# USB-RS485-unit.net
KiCad netlist of a schematic drawn in Altium Designer
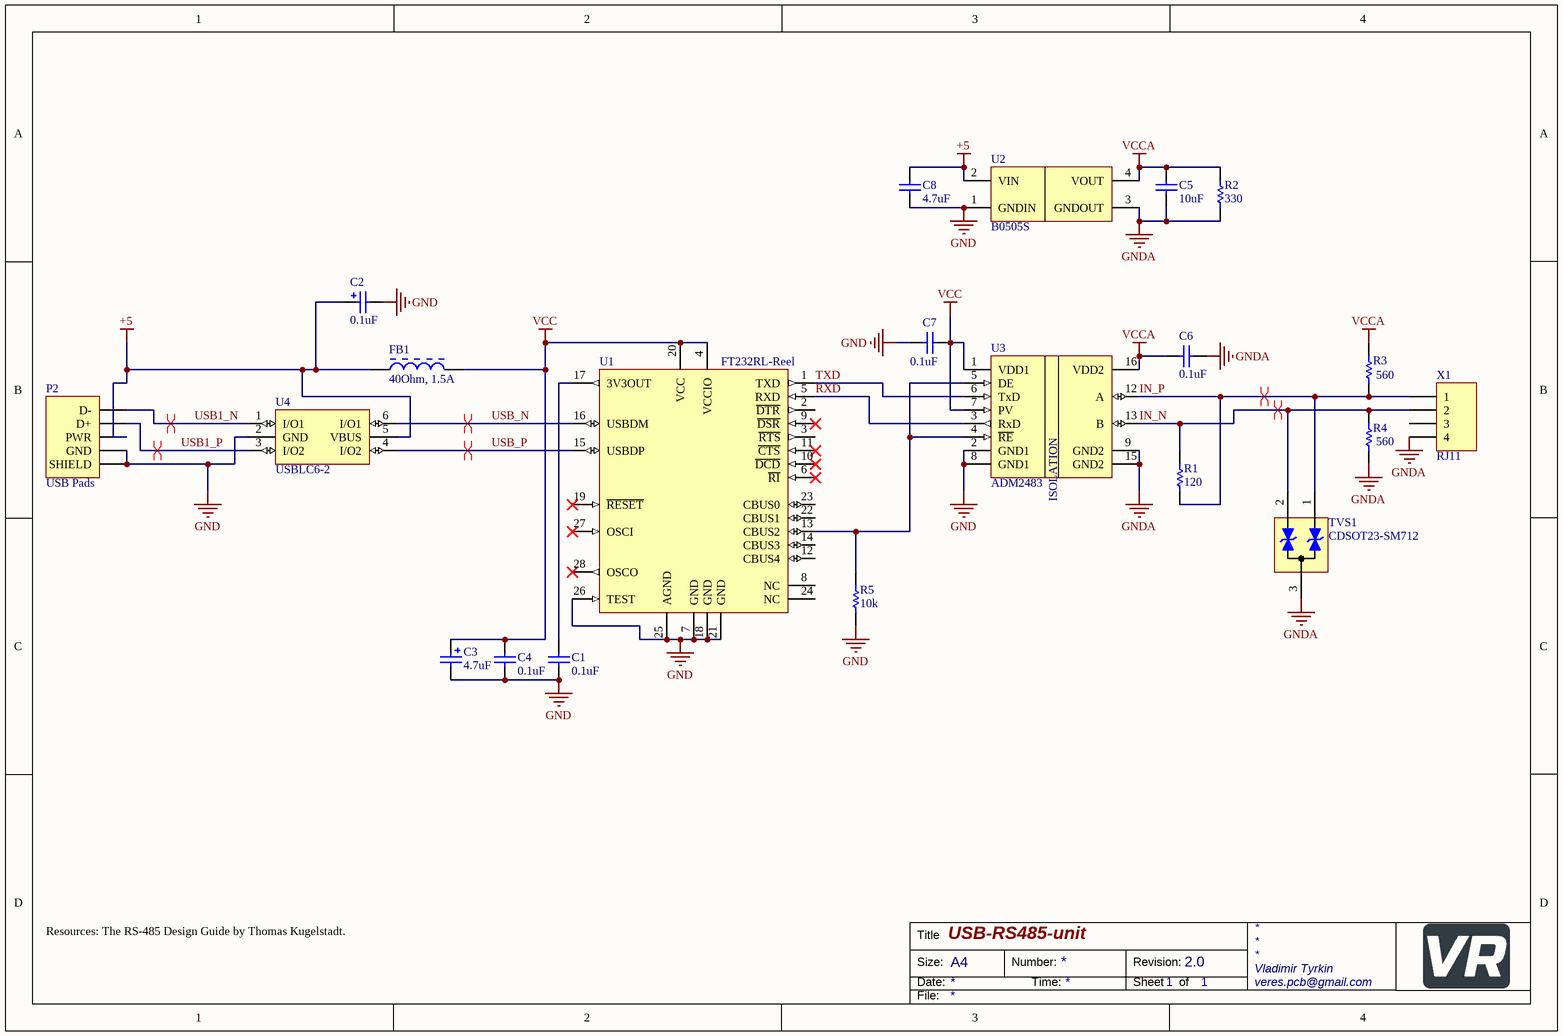
[diagram p0: USB-RS485-unit.SchDoc]

(export (version "E")
  (design (tool "Eeschema 10.0.6"))
  (components
    (comp (ref "C1")
      (value "0.1uF")
      (footprint "C1206")
      (description "Capacitor ceramic SMT")
      (fields
        (field (name "MANUFACTURER_PART_NUMBER") "GRM319R72A104KA01D")
        (field (name "MANUFACTURER") "Murata")
      )
      (libsource (lib "USB-RS485-unit") (part "Cap"))
    )
    (comp (ref "C2")
      (value "0.1uF")
      (footprint "TC3216-1206")
      (description "Polarized Capacitor SMT")
      (fields
        (field (name "MANUFACTURER") "TECAP")
        (field (name "MANUFACTURER_PART_NUMBER") "TECAP0.1/35VA10")
      )
      (libsource (lib "USB-RS485-unit") (part "Cap Polarized"))
    )
    (comp (ref "C3")
      (value "4.7uF")
      (footprint "TC3216-1206")
      (description "Polarized Capacitor SMT")
      (fields
        (field (name "MANUFACTURER") "TECAP")
        (field (name "MANUFACTURER_PART_NUMBER") "TECAP4.7/10VA10")
      )
      (libsource (lib "USB-RS485-unit") (part "Cap Polarized"))
    )
    (comp (ref "C4")
      (value "0.1uF")
      (footprint "C1206")
      (description "Capacitor ceramic SMT")
      (fields
        (field (name "MANUFACTURER_PART_NUMBER") "GRM319R72A104KA01D")
        (field (name "MANUFACTURER") "Murata")
      )
      (libsource (lib "USB-RS485-unit") (part "Cap"))
    )
    (comp (ref "C5")
      (value "10uF")
      (footprint "C1206")
      (description "Capacitor ceramic SMT")
      (fields
        (field (name "MANUFACTURER_PART_NUMBER") "GRM31CR61E106KA12L")
        (field (name "MANUFACTURER") "Murata")
      )
      (libsource (lib "USB-RS485-unit") (part "Cap"))
    )
    (comp (ref "C6")
      (value "0.1uF")
      (footprint "C1206")
      (description "Capacitor ceramic SMT")
      (fields
        (field (name "MANUFACTURER_PART_NUMBER") "GRM319R72A104KA01D")
        (field (name "MANUFACTURER") "Murata")
      )
      (libsource (lib "USB-RS485-unit") (part "Cap"))
    )
    (comp (ref "C7")
      (value "0.1uF")
      (footprint "C1206")
      (description "Capacitor ceramic SMT")
      (fields
        (field (name "MANUFACTURER_PART_NUMBER") "GRM319R72A104KA01D")
        (field (name "MANUFACTURER") "Murata")
      )
      (libsource (lib "USB-RS485-unit") (part "Cap"))
    )
    (comp (ref "C8")
      (value "4.7uF")
      (footprint "C1206")
      (description "Capacitor ceramic SMT")
      (fields
        (field (name "MANUFACTURER_PART_NUMBER") "GRM31CR71E475KA88L")
        (field (name "MANUFACTURER") "Murata")
      )
      (libsource (lib "USB-RS485-unit") (part "Cap"))
    )
    (comp (ref "FB1")
      (value "40Ohm, 1.5A")
      (footprint "WE-CBF_0805_High Speed")
      (description "Ferrite Bead")
      (fields
        (field (name "MANUFACTURER PART NUMBER") "MI0805K400R-10")
        (field (name "MANUFACTURER") "Laird Technologies")
      )
      (libsource (lib "WE-FerriteBead (rev21a)") (part "7427920"))
    )
    (comp (ref "P2")
      (value "USB Pads")
      (footprint "USB soldering pads")
      (description "Pads for soldering USB cable")
      (libsource (lib "USB-RS485-unit") (part "USB pads"))
    )
    (comp (ref "R1")
      (value "120")
      (footprint "RES-0805")
      (description "Rectangular Thick Film Chip Resistor")
      (fields
        (field (name "MANUFACTURER") "Yageo")
        (field (name "MANUFACTURER_PART_NUMBER") "RC0805FR-07120RL")
      )
      (libsource (lib "USB-RS485-unit") (part "Res"))
    )
    (comp (ref "R2")
      (value "330")
      (footprint "RES-1206")
      (description "Rectangular Thick Film Chip Resistor")
      (fields
        (field (name "MANUFACTURER") "Yageo")
        (field (name "MANUFACTURER_PART_NUMBER") "RC0805FR-07330RL")
      )
      (libsource (lib "USB-RS485-unit") (part "Res"))
    )
    (comp (ref "R3")
      (value "560")
      (footprint "RES-0805")
      (description "Rectangular Thick Film Chip Resistor")
      (fields
        (field (name "MANUFACTURER") "Yageo")
        (field (name "MANUFACTURER_PART_NUMBER") "RC0805FR-07560RL")
      )
      (libsource (lib "USB-RS485-unit") (part "Res"))
    )
    (comp (ref "R4")
      (value "560")
      (footprint "RES-0805")
      (description "Rectangular Thick Film Chip Resistor")
      (fields
        (field (name "MANUFACTURER") "Yageo")
        (field (name "MANUFACTURER_PART_NUMBER") "RC0805FR-07560RL")
      )
      (libsource (lib "USB-RS485-unit") (part "Res"))
    )
    (comp (ref "R5")
      (value "10k")
      (footprint "RES-0805")
      (description "Rectangular Thick Film Chip Resistor")
      (fields
        (field (name "MANUFACTURER") "Yageo")
        (field (name "MANUFACTURER_PART_NUMBER") "RC0805FR-0710KL")
      )
      (libsource (lib "USB-RS485-unit") (part "Res"))
    )
    (comp (ref "TVS1")
      (value "CDSOT23-SM712")
      (footprint "SOT-23B_N")
      (description "Surface Mount TVS Diode")
      (fields (field (name "MANUFACTURER") "Bourns"))
      (libsource (lib "USB-RS485-unit") (part "CDSOT23-SM712"))
    )
    (comp (ref "U1")
      (value "FT232RL-Reel")
      (footprint "SSOP-28_L")
      (description "USB UART Asynchronous Serial Data Transfer Chip, SSOP-28, Tape and Reel")
      (fields (field (name "MANUFACTURER") "FTDI"))
      (libsource (lib "FTDI Communication UART") (part "FT232RL-Reel"))
    )
    (comp (ref "U2")
      (value "B0505S")
      (footprint "B0505S - horizontal")
      (description "Isolated DC-DC Converter")
      (fields
        (field (name "MANUFACTURER_PART_NUMBER") "B0505S-1WR2")
        (field (name "MANUFACTURER") "Mornsun Power")
      )
      (libsource (lib "USB-RS485-unit") (part "B0505S"))
    )
    (comp (ref "U3")
      (value "ADM2483")
      (footprint "SOL-16 Wide")
      (description "Half-Duplex, Isolated RS-485 Transceiver")
      (fields
        (field (name "MANUFACTURER_PART_NUMBER") "ADM2483BRWZ-REEL")
        (field (name "MANUFACTURER") "STMICROELECTRONICS")
      )
      (libsource (lib "USB-RS485-unit") (part "ADM2483"))
    )
    (comp (ref "U4")
      (value "USBLC6-2")
      (footprint "SOT23-6")
      (description "Quad Bidir ESD protection")
      (fields
        (field (name "MANUFACTURER") "STMICROELECTRONICS")
        (field (name "MANUFACTURER_PART_NUMBER") "USBLC6-2SC6")
      )
      (libsource (lib "USB-RS485-unit") (part "USBLC6-2"))
    )
    (comp (ref "X1")
      (value "RJ11")
      (footprint "RJ11")
      (description "RJ-11 Connector, 4-Pin")
      (fields
        (field (name "MANUFACTURER_PART_NUMBER") "DS1132-S40BPX")
        (field (name "MANUFACTURER") "Connfly")
      )
      (libsource (lib "USB-RS485-unit") (part "RJ11"))
    )
  )
  (nets
    (net (code "1") (name "+5") (class "Default")
      (node (ref "C2") (pin "1") (pinfunction "1_1") (pintype "passive"))
      (node (ref "C8") (pin "2") (pinfunction "2_2") (pintype "passive"))
      (node (ref "FB1") (pin "1") (pinfunction "1_1") (pintype "passive"))
      (node (ref "P2") (pin "3") (pinfunction "PWR_3") (pintype "power_in"))
      (node (ref "U2") (pin "2") (pinfunction "VIN_2") (pintype "power_in"))
      (node (ref "U4") (pin "5") (pinfunction "VBUS_5") (pintype "power_in"))
    )
    (net (code "2") (name "/IN_N") (class "Default")
      (node (ref "R1") (pin "2") (pinfunction "2_2") (pintype "passive"))
      (node (ref "R4") (pin "2") (pinfunction "2_2") (pintype "passive"))
      (node (ref "TVS1") (pin "2") (pintype "passive"))
      (node (ref "U3") (pin "13") (pinfunction "B_13") (pintype "bidirectional"))
      (node (ref "X1") (pin "2") (pinfunction "2_2") (pintype "passive"))
    )
    (net (code "3") (name "/IN_P") (class "Default")
      (node (ref "R1") (pin "1") (pinfunction "1_1") (pintype "passive"))
      (node (ref "R3") (pin "1") (pinfunction "1_1") (pintype "passive"))
      (node (ref "TVS1") (pin "1") (pintype "passive"))
      (node (ref "U3") (pin "12") (pinfunction "A_12") (pintype "bidirectional"))
      (node (ref "X1") (pin "1") (pinfunction "1_1") (pintype "passive"))
    )
    (net (code "4") (name "/RXD") (class "Default")
      (node (ref "U1") (pin "5") (pinfunction "RXD_5") (pintype "input"))
      (node (ref "U3") (pin "3") (pinfunction "RxD_3") (pintype "output"))
    )
    (net (code "5") (name "/TXD") (class "Default")
      (node (ref "U1") (pin "1") (pinfunction "TXD_1") (pintype "output"))
      (node (ref "U3") (pin "6") (pinfunction "TxD_6") (pintype "input"))
    )
    (net (code "6") (name "/USB1_N") (class "Default")
      (node (ref "P2") (pin "1") (pinfunction "D-_1") (pintype "passive"))
      (node (ref "U4") (pin "1") (pinfunction "I/O1_1") (pintype "bidirectional"))
    )
    (net (code "7") (name "/USB1_P") (class "Default")
      (node (ref "P2") (pin "2") (pinfunction "D+_2") (pintype "passive"))
      (node (ref "U4") (pin "3") (pinfunction "I/O2_3") (pintype "bidirectional"))
    )
    (net (code "8") (name "/USB_N") (class "Default")
      (node (ref "U1") (pin "16") (pinfunction "USBDM_16") (pintype "bidirectional"))
      (node (ref "U4") (pin "6") (pinfunction "I/O1_6") (pintype "bidirectional"))
    )
    (net (code "9") (name "/USB_P") (class "Default")
      (node (ref "U1") (pin "15") (pinfunction "USBDP_15") (pintype "bidirectional"))
      (node (ref "U4") (pin "4") (pinfunction "I/O2_4") (pintype "bidirectional"))
    )
    (net (code "10") (name "GND") (class "Default")
      (node (ref "C1") (pin "1") (pinfunction "1_1") (pintype "passive"))
      (node (ref "C2") (pin "2") (pinfunction "2_2") (pintype "passive"))
      (node (ref "C3") (pin "2") (pinfunction "2_2") (pintype "passive"))
      (node (ref "C4") (pin "1") (pinfunction "1_1") (pintype "passive"))
      (node (ref "C7") (pin "1") (pinfunction "1_1") (pintype "passive"))
      (node (ref "C8") (pin "1") (pinfunction "1_1") (pintype "passive"))
      (node (ref "P2") (pin "4") (pinfunction "GND_4") (pintype "power_in"))
      (node (ref "P2") (pin "5") (pinfunction "SHIELD_5") (pintype "power_in"))
      (node (ref "R5") (pin "1") (pinfunction "1_1") (pintype "passive"))
      (node (ref "U1") (pin "18") (pinfunction "GND_18") (pintype "power_in"))
      (node (ref "U1") (pin "21") (pinfunction "GND_21") (pintype "power_in"))
      (node (ref "U1") (pin "25") (pinfunction "AGND_25") (pintype "power_in"))
      (node (ref "U1") (pin "26") (pinfunction "TEST_26") (pintype "input"))
      (node (ref "U1") (pin "7") (pinfunction "GND_7") (pintype "power_in"))
      (node (ref "U2") (pin "1") (pinfunction "GNDIN_1") (pintype "power_in"))
      (node (ref "U3") (pin "2") (pinfunction "GND1_2") (pintype "power_in"))
      (node (ref "U3") (pin "8") (pinfunction "GND1_8") (pintype "power_in"))
      (node (ref "U4") (pin "2") (pinfunction "GND_2") (pintype "power_in"))
    )
    (net (code "11") (name "GNDA") (class "Default")
      (node (ref "C5") (pin "1") (pinfunction "1_1") (pintype "passive"))
      (node (ref "C6") (pin "1") (pinfunction "1_1") (pintype "passive"))
      (node (ref "R2") (pin "1") (pinfunction "1_1") (pintype "passive"))
      (node (ref "R4") (pin "1") (pinfunction "1_1") (pintype "passive"))
      (node (ref "TVS1") (pin "3") (pintype "passive"))
      (node (ref "U2") (pin "3") (pinfunction "GNDOUT_3") (pintype "power_in"))
      (node (ref "U3") (pin "15") (pinfunction "GND2_15") (pintype "power_in"))
      (node (ref "U3") (pin "9") (pinfunction "GND2_9") (pintype "power_in"))
      (node (ref "X1") (pin "4") (pinfunction "4_4") (pintype "passive"))
    )
    (net (code "12") (name "Net-(U1-3V3OUT)") (class "Default")
      (node (ref "C1") (pin "2") (pinfunction "2_2") (pintype "passive"))
      (node (ref "U1") (pin "17") (pinfunction "3V3OUT_17") (pintype "output"))
    )
    (net (code "13") (name "Net-(U1-CBUS2)") (class "Default")
      (node (ref "R5") (pin "2") (pinfunction "2_2") (pintype "passive"))
      (node (ref "U1") (pin "13") (pinfunction "CBUS2_13") (pintype "bidirectional"))
      (node (ref "U3") (pin "4") (pinfunction "~{RE}_4") (pintype "input"))
      (node (ref "U3") (pin "5") (pinfunction "DE_5") (pintype "input"))
    )
    (net (code "14") (name "VCC") (class "Default")
      (node (ref "C3") (pin "1") (pinfunction "1_1") (pintype "passive"))
      (node (ref "C4") (pin "2") (pinfunction "2_2") (pintype "passive"))
      (node (ref "C7") (pin "2") (pinfunction "2_2") (pintype "passive"))
      (node (ref "FB1") (pin "2") (pinfunction "2_2") (pintype "passive"))
      (node (ref "U1") (pin "20") (pinfunction "VCC_20") (pintype "power_in"))
      (node (ref "U1") (pin "4") (pinfunction "VCCIO_4") (pintype "power_in"))
      (node (ref "U3") (pin "1") (pinfunction "VDD1_1") (pintype "power_in"))
      (node (ref "U3") (pin "7") (pinfunction "PV_7") (pintype "input"))
    )
    (net (code "15") (name "VCCA") (class "Default")
      (node (ref "C5") (pin "2") (pinfunction "2_2") (pintype "passive"))
      (node (ref "C6") (pin "2") (pinfunction "2_2") (pintype "passive"))
      (node (ref "R2") (pin "2") (pinfunction "2_2") (pintype "passive"))
      (node (ref "R3") (pin "2") (pinfunction "2_2") (pintype "passive"))
      (node (ref "U2") (pin "4") (pinfunction "VOUT_4") (pintype "power_in"))
      (node (ref "U3") (pin "16") (pinfunction "VDD2_16") (pintype "power_in"))
    )
    (net (code "16") (name "unconnected-(U1-CBUS0-Pad23)") (class "Default")
      (node (ref "U1") (pin "23") (pinfunction "CBUS0_23") (pintype "bidirectional"))
    )
    (net (code "17") (name "unconnected-(U1-CBUS1-Pad22)") (class "Default")
      (node (ref "U1") (pin "22") (pinfunction "CBUS1_22") (pintype "bidirectional"))
    )
    (net (code "18") (name "unconnected-(U1-CBUS3-Pad14)") (class "Default")
      (node (ref "U1") (pin "14") (pinfunction "CBUS3_14") (pintype "bidirectional"))
    )
    (net (code "19") (name "unconnected-(U1-CBUS4-Pad12)") (class "Default")
      (node (ref "U1") (pin "12") (pinfunction "CBUS4_12") (pintype "bidirectional"))
    )
    (net (code "20") (name "unconnected-(U1-NC-Pad8)") (class "Default")
      (node (ref "U1") (pin "8") (pinfunction "NC_8") (pintype "passive"))
    )
    (net (code "21") (name "unconnected-(U1-NC-Pad24)") (class "Default")
      (node (ref "U1") (pin "24") (pinfunction "NC_24") (pintype "passive"))
    )
    (net (code "22") (name "unconnected-(U1-OSCI-Pad27)") (class "Default")
      (node (ref "U1") (pin "27") (pinfunction "OSCI_27") (pintype "input+no_connect"))
    )
    (net (code "23") (name "unconnected-(U1-OSCO-Pad28)") (class "Default")
      (node (ref "U1") (pin "28") (pinfunction "OSCO_28") (pintype "output+no_connect"))
    )
    (net (code "24") (name "unconnected-(U1-~{CTS}-Pad11)") (class "Default")
      (node (ref "U1") (pin "11") (pinfunction "~{CTS}_11") (pintype "input+no_connect"))
    )
    (net (code "25") (name "unconnected-(U1-~{DCD}-Pad10)") (class "Default")
      (node (ref "U1") (pin "10") (pinfunction "~{DCD}_10") (pintype "input+no_connect"))
    )
    (net (code "26") (name "unconnected-(U1-~{DSR}-Pad9)") (class "Default")
      (node (ref "U1") (pin "9") (pinfunction "~{DSR}_9") (pintype "input+no_connect"))
    )
    (net (code "27") (name "unconnected-(U1-~{DTR}-Pad2)") (class "Default")
      (node (ref "U1") (pin "2") (pinfunction "~{DTR}_2") (pintype "output"))
    )
    (net (code "28") (name "unconnected-(U1-~{RESET}-Pad19)") (class "Default")
      (node (ref "U1") (pin "19") (pinfunction "~{RESET}_19") (pintype "input+no_connect"))
    )
    (net (code "29") (name "unconnected-(U1-~{RI}-Pad6)") (class "Default")
      (node (ref "U1") (pin "6") (pinfunction "~{RI}_6") (pintype "input+no_connect"))
    )
    (net (code "30") (name "unconnected-(U1-~{RTS}-Pad3)") (class "Default")
      (node (ref "U1") (pin "3") (pinfunction "~{RTS}_3") (pintype "output"))
    )
    (net (code "31") (name "unconnected-(X1-Pad3)") (class "Default")
      (node (ref "X1") (pin "3") (pinfunction "3_3") (pintype "passive"))
    )
  )
)
